# BV100011_SDCARD.net
KiCad netlist of a schematic drawn in Altium Designer
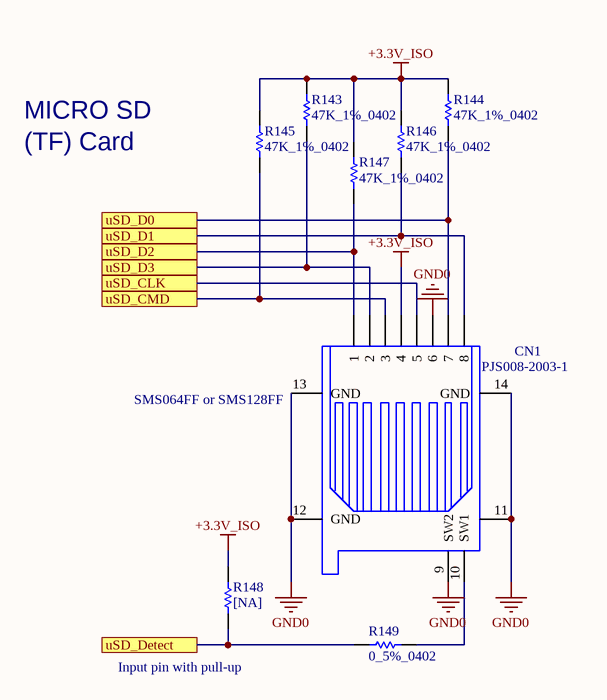
[diagram p0: BV100011_SDCARD.SchDoc]

(export (version "E")
  (design (tool "Eeschema 10.0.6"))
  (components
    (comp (ref "CN1")
      (value "PJS008-2003-1")
      (footprint "PJS008-2003-1")
      (description "Memory Card Connectors MicroSD Card Conn Revrs Mnt Push-Push")
      (libsource (lib "Mb1191") (part "microSD-PJS008-2003"))
    )
    (comp (ref "R143")
      (value "47K_1%_0402")
      (footprint "0402R")
      (description "Resistor,47K,0402,1%,YAGEO")
      (libsource (lib "MCD_TOOLS") (part "Res_47K_1%_0402"))
    )
    (comp (ref "R144")
      (value "47K_1%_0402")
      (footprint "0402R")
      (description "Resistor,47K,0402,1%,YAGEO")
      (libsource (lib "MCD_TOOLS") (part "Res_47K_1%_0402"))
    )
    (comp (ref "R145")
      (value "47K_1%_0402")
      (footprint "0402R")
      (description "Resistor,47K,0402,1%,YAGEO")
      (libsource (lib "MCD_TOOLS") (part "Res_47K_1%_0402"))
    )
    (comp (ref "R146")
      (value "47K_1%_0402")
      (footprint "0402R")
      (description "Resistor,47K,0402,1%,YAGEO")
      (libsource (lib "MCD_TOOLS") (part "Res_47K_1%_0402"))
    )
    (comp (ref "R147")
      (value "47K_1%_0402")
      (footprint "0402R")
      (description "Resistor,47K,0402,1%,YAGEO")
      (libsource (lib "MCD_TOOLS") (part "Res_47K_1%_0402"))
    )
    (comp (ref "R148")
      (value "[NA]")
      (footprint "0402R")
      (description "Resistor,[NA],0402")
      (libsource (lib "MCD_TOOLS") (part "Res_NA_0402"))
    )
    (comp (ref "R149")
      (value "0_5%_0402")
      (footprint "0402R")
      (description "Resistor,0,0402,5%,YAGEO")
      (libsource (lib "MCD_TOOLS") (part "Res_0_5%_0402"))
    )
  )
  (nets
    (net (code "1") (name "+3.3V_ISO") (class "Default")
      (node (ref "CN1") (pin "4") (pinfunction "4_4") (pintype "passive"))
      (node (ref "R143") (pin "2") (pinfunction "2_2") (pintype "passive"))
      (node (ref "R144") (pin "2") (pinfunction "2_2") (pintype "passive"))
      (node (ref "R145") (pin "2") (pinfunction "2_2") (pintype "passive"))
      (node (ref "R146") (pin "2") (pinfunction "2_2") (pintype "passive"))
      (node (ref "R147") (pin "2") (pinfunction "2_2") (pintype "passive"))
      (node (ref "R148") (pin "2") (pinfunction "2_2") (pintype "passive"))
    )
    (net (code "2") (name "/uSD_CLK") (class "Default")
      (node (ref "CN1") (pin "5") (pinfunction "5_5") (pintype "passive"))
    )
    (net (code "3") (name "/uSD_CMD") (class "Default")
      (node (ref "CN1") (pin "3") (pinfunction "3_3") (pintype "passive"))
      (node (ref "R145") (pin "1") (pinfunction "1_1") (pintype "passive"))
    )
    (net (code "4") (name "/uSD_D0") (class "Default")
      (node (ref "CN1") (pin "7") (pinfunction "7_7") (pintype "passive"))
      (node (ref "R144") (pin "1") (pinfunction "1_1") (pintype "passive"))
    )
    (net (code "5") (name "/uSD_D1") (class "Default")
      (node (ref "CN1") (pin "8") (pinfunction "8_8") (pintype "passive"))
      (node (ref "R146") (pin "1") (pinfunction "1_1") (pintype "passive"))
    )
    (net (code "6") (name "/uSD_D2") (class "Default")
      (node (ref "CN1") (pin "1") (pinfunction "1_1") (pintype "passive"))
      (node (ref "R147") (pin "1") (pinfunction "1_1") (pintype "passive"))
    )
    (net (code "7") (name "/uSD_D3") (class "Default")
      (node (ref "CN1") (pin "2") (pinfunction "2_2") (pintype "passive"))
      (node (ref "R143") (pin "1") (pinfunction "1_1") (pintype "passive"))
    )
    (net (code "8") (name "/uSD_Detect") (class "Default")
      (node (ref "R148") (pin "1") (pinfunction "1_1") (pintype "passive"))
      (node (ref "R149") (pin "1") (pinfunction "1_1") (pintype "passive"))
    )
    (net (code "9") (name "GND0") (class "Default")
      (node (ref "CN1") (pin "11") (pinfunction "GND_11") (pintype "passive"))
      (node (ref "CN1") (pin "12") (pinfunction "GND_12") (pintype "passive"))
      (node (ref "CN1") (pin "13") (pinfunction "GND_13") (pintype "passive"))
      (node (ref "CN1") (pin "14") (pinfunction "GND_14") (pintype "passive"))
      (node (ref "CN1") (pin "6") (pinfunction "6_6") (pintype "passive"))
      (node (ref "CN1") (pin "9") (pinfunction "SW2_9") (pintype "passive"))
    )
    (net (code "10") (name "Net-(CN1-SW1)") (class "Default")
      (node (ref "CN1") (pin "10") (pinfunction "SW1_10") (pintype "passive"))
      (node (ref "R149") (pin "2") (pinfunction "2_2") (pintype "passive"))
    )
  )
)
